# ADS1299.net
KiCad netlist of a schematic drawn in Altium Designer
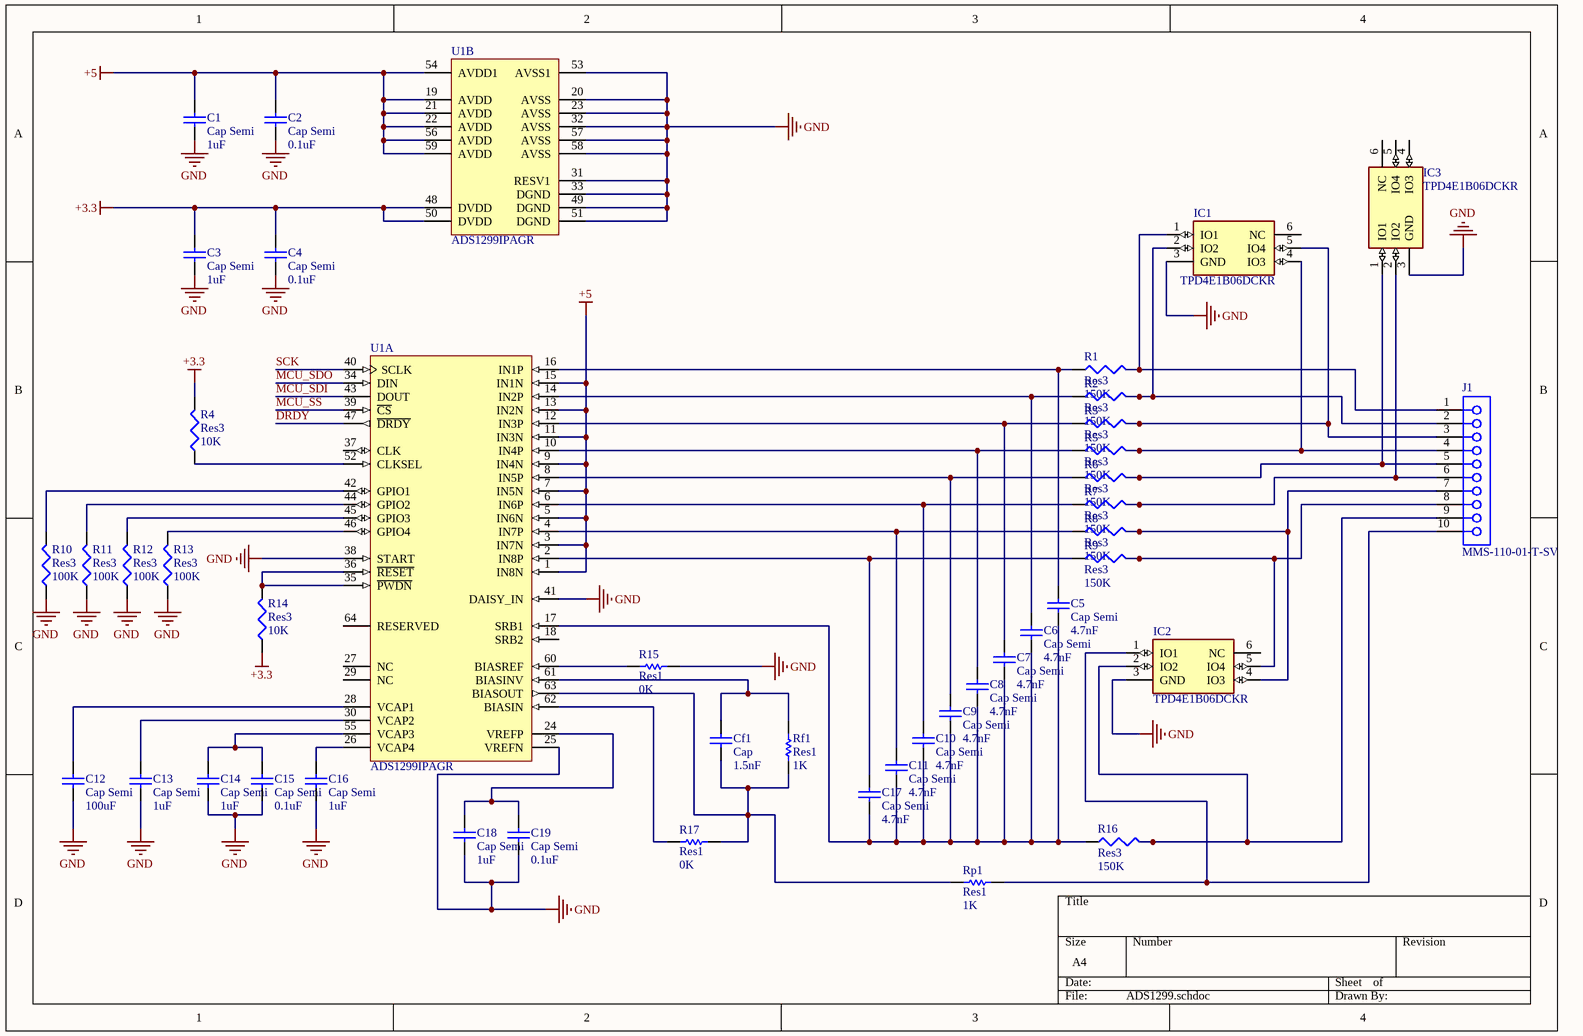
[diagram p0: ADS1299.schdoc]

(export (version "E")
  (design (tool "Eeschema 10.0.6"))
  (components
    (comp (ref "C1")
      (value "Cap Semi")
      (footprint "0805c")
      (description "Capacitor (Semiconductor SIM Model)")
      (fields (field (name "ALTIUM_VALUE") "1uF") (field (name "PUBLISHER") "Altium Limited"))
      (libsource (lib "Miscellaneous Devices") (part "Cap Semi"))
    )
    (comp (ref "C2")
      (value "Cap Semi")
      (footprint "0805c")
      (description "Capacitor (Semiconductor SIM Model)")
      (fields (field (name "ALTIUM_VALUE") "0.1uF") (field (name "PUBLISHER") "Altium Limited"))
      (libsource (lib "Miscellaneous Devices") (part "Cap Semi"))
    )
    (comp (ref "C3")
      (value "Cap Semi")
      (footprint "0805c")
      (description "Capacitor (Semiconductor SIM Model)")
      (fields (field (name "ALTIUM_VALUE") "1uF") (field (name "PUBLISHER") "Altium Limited"))
      (libsource (lib "Miscellaneous Devices") (part "Cap Semi"))
    )
    (comp (ref "C4")
      (value "Cap Semi")
      (footprint "0805c")
      (description "Capacitor (Semiconductor SIM Model)")
      (fields (field (name "ALTIUM_VALUE") "0.1uF") (field (name "PUBLISHER") "Altium Limited"))
      (libsource (lib "Miscellaneous Devices") (part "Cap Semi"))
    )
    (comp (ref "C5")
      (value "Cap Semi")
      (footprint "0805c")
      (description "Capacitor (Semiconductor SIM Model)")
      (fields (field (name "ALTIUM_VALUE") "4.7nF") (field (name "PUBLISHER") "Altium Limited"))
      (libsource (lib "Miscellaneous Devices") (part "Cap Semi"))
    )
    (comp (ref "C6")
      (value "Cap Semi")
      (footprint "0805c")
      (description "Capacitor (Semiconductor SIM Model)")
      (fields (field (name "ALTIUM_VALUE") "4.7nF") (field (name "PUBLISHER") "Altium Limited"))
      (libsource (lib "Miscellaneous Devices") (part "Cap Semi"))
    )
    (comp (ref "C7")
      (value "Cap Semi")
      (footprint "0805c")
      (description "Capacitor (Semiconductor SIM Model)")
      (fields (field (name "ALTIUM_VALUE") "4.7nF") (field (name "PUBLISHER") "Altium Limited"))
      (libsource (lib "Miscellaneous Devices") (part "Cap Semi"))
    )
    (comp (ref "C8")
      (value "Cap Semi")
      (footprint "0805c")
      (description "Capacitor (Semiconductor SIM Model)")
      (fields (field (name "ALTIUM_VALUE") "4.7nF") (field (name "PUBLISHER") "Altium Limited"))
      (libsource (lib "Miscellaneous Devices") (part "Cap Semi"))
    )
    (comp (ref "C9")
      (value "Cap Semi")
      (footprint "0805c")
      (description "Capacitor (Semiconductor SIM Model)")
      (fields (field (name "ALTIUM_VALUE") "4.7nF") (field (name "PUBLISHER") "Altium Limited"))
      (libsource (lib "Miscellaneous Devices") (part "Cap Semi"))
    )
    (comp (ref "C10")
      (value "Cap Semi")
      (footprint "0805c")
      (description "Capacitor (Semiconductor SIM Model)")
      (fields (field (name "ALTIUM_VALUE") "4.7nF") (field (name "PUBLISHER") "Altium Limited"))
      (libsource (lib "Miscellaneous Devices") (part "Cap Semi"))
    )
    (comp (ref "C11")
      (value "Cap Semi")
      (footprint "0805c")
      (description "Capacitor (Semiconductor SIM Model)")
      (fields (field (name "ALTIUM_VALUE") "4.7nF") (field (name "PUBLISHER") "Altium Limited"))
      (libsource (lib "Miscellaneous Devices") (part "Cap Semi"))
    )
    (comp (ref "C12")
      (value "Cap Semi")
      (footprint "0805c")
      (description "Capacitor (Semiconductor SIM Model)")
      (fields (field (name "ALTIUM_VALUE") "100uF") (field (name "PUBLISHER") "Altium Limited"))
      (libsource (lib "Miscellaneous Devices") (part "Cap Semi"))
    )
    (comp (ref "C13")
      (value "Cap Semi")
      (footprint "0805c")
      (description "Capacitor (Semiconductor SIM Model)")
      (fields (field (name "ALTIUM_VALUE") "1uF") (field (name "PUBLISHER") "Altium Limited"))
      (libsource (lib "Miscellaneous Devices") (part "Cap Semi"))
    )
    (comp (ref "C14")
      (value "Cap Semi")
      (footprint "0805c")
      (description "Capacitor (Semiconductor SIM Model)")
      (fields (field (name "ALTIUM_VALUE") "1uF") (field (name "PUBLISHER") "Altium Limited"))
      (libsource (lib "Miscellaneous Devices") (part "Cap Semi"))
    )
    (comp (ref "C15")
      (value "Cap Semi")
      (footprint "0805c")
      (description "Capacitor (Semiconductor SIM Model)")
      (fields (field (name "ALTIUM_VALUE") "0.1uF") (field (name "PUBLISHER") "Altium Limited"))
      (libsource (lib "Miscellaneous Devices") (part "Cap Semi"))
    )
    (comp (ref "C16")
      (value "Cap Semi")
      (footprint "0805c")
      (description "Capacitor (Semiconductor SIM Model)")
      (fields (field (name "ALTIUM_VALUE") "1uF") (field (name "PUBLISHER") "Altium Limited"))
      (libsource (lib "Miscellaneous Devices") (part "Cap Semi"))
    )
    (comp (ref "C17")
      (value "Cap Semi")
      (footprint "0805c")
      (description "Capacitor (Semiconductor SIM Model)")
      (fields (field (name "ALTIUM_VALUE") "4.7nF") (field (name "PUBLISHER") "Altium Limited"))
      (libsource (lib "Miscellaneous Devices") (part "Cap Semi"))
    )
    (comp (ref "C18")
      (value "Cap Semi")
      (footprint "0805c")
      (description "Capacitor (Semiconductor SIM Model)")
      (fields (field (name "ALTIUM_VALUE") "1uF") (field (name "PUBLISHER") "Altium Limited"))
      (libsource (lib "Miscellaneous Devices") (part "Cap Semi"))
    )
    (comp (ref "C19")
      (value "Cap Semi")
      (footprint "0805c")
      (description "Capacitor (Semiconductor SIM Model)")
      (fields (field (name "ALTIUM_VALUE") "0.1uF") (field (name "PUBLISHER") "Altium Limited"))
      (libsource (lib "Miscellaneous Devices") (part "Cap Semi"))
    )
    (comp (ref "Cf1")
      (value "Cap")
      (footprint "102")
      (description "Capacitor")
      (fields (field (name "ALTIUM_VALUE") "1.5nF") (field (name "PUBLISHER") "Altium Limited"))
      (libsource (lib "Miscellaneous Devices") (part "Cap"))
    )
    (comp (ref "IC1")
      (value "TPD4E1B06DCKR")
      (footprint "SOT363")
      (description "Integrated Circuit")
      (fields
        (field (name "MOUSER PART NUMBER") "595-TPD4E1B06DCKR")
        (field (name "RS PART NUMBER") "8255330P")
      )
      (libsource (lib "") (part "TPD4E1B06DCKR_1"))
    )
    (comp (ref "IC2")
      (value "TPD4E1B06DCKR")
      (footprint "SOT363")
      (description "Integrated Circuit")
      (fields
        (field (name "MOUSER PART NUMBER") "595-TPD4E1B06DCKR")
        (field (name "RS PART NUMBER") "8255330P")
      )
      (libsource (lib "") (part "TPD4E1B06DCKR_1"))
    )
    (comp (ref "IC3")
      (value "TPD4E1B06DCKR")
      (footprint "SOT363")
      (description "Integrated Circuit")
      (fields
        (field (name "MOUSER PART NUMBER") "595-TPD4E1B06DCKR")
        (field (name "RS PART NUMBER") "8255330P")
      )
      (libsource (lib "*") (part "TPD4E1B06DCKR"))
    )
    (comp (ref "J1")
      (value "MMS-110-01-T-SV")
      (footprint "HDR1X10")
      (fields (field (name "MANUFACTURER") "Samtec"))
      (libsource (lib "Altium Content Vault") (part "SMTC-MMS-110-01-X-SV"))
    )
    (comp (ref "R1")
      (value "Res3")
      (footprint "0805")
      (description "Resistor")
      (fields (field (name "ALTIUM_VALUE") "150K") (field (name "PUBLISHER") "Altium Limited"))
      (libsource (lib "Miscellaneous Devices") (part "Res3"))
    )
    (comp (ref "R2")
      (value "Res3")
      (footprint "0805")
      (description "Resistor")
      (fields (field (name "ALTIUM_VALUE") "150K") (field (name "PUBLISHER") "Altium Limited"))
      (libsource (lib "Miscellaneous Devices") (part "Res3"))
    )
    (comp (ref "R3")
      (value "Res3")
      (footprint "0805")
      (description "Resistor")
      (fields (field (name "ALTIUM_VALUE") "150K") (field (name "PUBLISHER") "Altium Limited"))
      (libsource (lib "Miscellaneous Devices") (part "Res3"))
    )
    (comp (ref "R4")
      (value "Res3")
      (footprint "0805")
      (description "Resistor")
      (fields (field (name "ALTIUM_VALUE") "10K") (field (name "PUBLISHER") "Altium Limited"))
      (libsource (lib "Miscellaneous Devices") (part "Res3"))
    )
    (comp (ref "R5")
      (value "Res3")
      (footprint "0805")
      (description "Resistor")
      (fields (field (name "ALTIUM_VALUE") "150K") (field (name "PUBLISHER") "Altium Limited"))
      (libsource (lib "Miscellaneous Devices") (part "Res3"))
    )
    (comp (ref "R6")
      (value "Res3")
      (footprint "0805")
      (description "Resistor")
      (fields (field (name "ALTIUM_VALUE") "150K") (field (name "PUBLISHER") "Altium Limited"))
      (libsource (lib "Miscellaneous Devices") (part "Res3"))
    )
    (comp (ref "R7")
      (value "Res3")
      (footprint "0805")
      (description "Resistor")
      (fields (field (name "ALTIUM_VALUE") "150K") (field (name "PUBLISHER") "Altium Limited"))
      (libsource (lib "Miscellaneous Devices") (part "Res3"))
    )
    (comp (ref "R8")
      (value "Res3")
      (footprint "0805")
      (description "Resistor")
      (fields (field (name "ALTIUM_VALUE") "150K") (field (name "PUBLISHER") "Altium Limited"))
      (libsource (lib "Miscellaneous Devices") (part "Res3"))
    )
    (comp (ref "R9")
      (value "Res3")
      (footprint "0805")
      (description "Resistor")
      (fields (field (name "ALTIUM_VALUE") "150K") (field (name "PUBLISHER") "Altium Limited"))
      (libsource (lib "Miscellaneous Devices") (part "Res3"))
    )
    (comp (ref "R10")
      (value "Res3")
      (footprint "0805")
      (description "Resistor")
      (fields (field (name "ALTIUM_VALUE") "100K") (field (name "PUBLISHER") "Altium Limited"))
      (libsource (lib "Miscellaneous Devices") (part "Res3"))
    )
    (comp (ref "R11")
      (value "Res3")
      (footprint "0805")
      (description "Resistor")
      (fields (field (name "ALTIUM_VALUE") "100K") (field (name "PUBLISHER") "Altium Limited"))
      (libsource (lib "Miscellaneous Devices") (part "Res3"))
    )
    (comp (ref "R12")
      (value "Res3")
      (footprint "0805")
      (description "Resistor")
      (fields (field (name "ALTIUM_VALUE") "100K") (field (name "PUBLISHER") "Altium Limited"))
      (libsource (lib "Miscellaneous Devices") (part "Res3"))
    )
    (comp (ref "R13")
      (value "Res3")
      (footprint "0805")
      (description "Resistor")
      (fields (field (name "ALTIUM_VALUE") "100K") (field (name "PUBLISHER") "Altium Limited"))
      (libsource (lib "Miscellaneous Devices") (part "Res3"))
    )
    (comp (ref "R14")
      (value "Res3")
      (footprint "0805")
      (description "Resistor")
      (fields (field (name "ALTIUM_VALUE") "10K") (field (name "PUBLISHER") "Altium Limited"))
      (libsource (lib "Miscellaneous Devices") (part "Res3"))
    )
    (comp (ref "R15")
      (value "Res1")
      (footprint "RB0.4    &9")
      (description "Resistor")
      (fields (field (name "ALTIUM_VALUE") "0K") (field (name "PUBLISHER") "Altium Limited"))
      (libsource (lib "Miscellaneous Devices") (part "Res1"))
    )
    (comp (ref "R16")
      (value "Res3")
      (footprint "0805")
      (description "Resistor")
      (fields (field (name "ALTIUM_VALUE") "150K") (field (name "PUBLISHER") "Altium Limited"))
      (libsource (lib "Miscellaneous Devices") (part "Res3"))
    )
    (comp (ref "R17")
      (value "Res1")
      (footprint "RB0.4    &9")
      (description "Resistor")
      (fields (field (name "ALTIUM_VALUE") "0K") (field (name "PUBLISHER") "Altium Limited"))
      (libsource (lib "Miscellaneous Devices") (part "Res1"))
    )
    (comp (ref "Rf1")
      (value "Res1")
      (footprint "RB0.4    &9")
      (description "Resistor")
      (fields (field (name "ALTIUM_VALUE") "1K") (field (name "PUBLISHER") "Altium Limited"))
      (libsource (lib "Miscellaneous Devices") (part "Res1"))
    )
    (comp (ref "Rp1")
      (value "Res1")
      (footprint "RB0.4    &9")
      (description "Resistor")
      (fields (field (name "ALTIUM_VALUE") "1K") (field (name "PUBLISHER") "Altium Limited"))
      (libsource (lib "Miscellaneous Devices") (part "Res1"))
    )
    (comp (ref "U1")
      (value "ADS1299IPAGR")
      (footprint "TQFP64_N")
      (fields (field (name "MANUFACTURER") "Texas Instruments"))
      (libsource (lib "Altium Content Vault") (part "TI-ADS1299-PAG-64"))
    )
  )
  (nets
    (net (code "1") (name "+3.3") (class "Default")
      (node (ref "C3") (pin "2") (pinfunction "2_2") (pintype "passive"))
      (node (ref "C4") (pin "2") (pinfunction "2_2") (pintype "passive"))
      (node (ref "R14") (pin "1") (pinfunction "1_1") (pintype "passive"))
      (node (ref "R4") (pin "2") (pinfunction "2_2") (pintype "passive"))
      (node (ref "U1") (pin "48") (pinfunction "DVDD_48") (pintype "power_in"))
      (node (ref "U1") (pin "50") (pinfunction "DVDD_50") (pintype "power_in"))
    )
    (net (code "2") (name "+5") (class "Default")
      (node (ref "C1") (pin "2") (pinfunction "2_2") (pintype "passive"))
      (node (ref "C2") (pin "2") (pinfunction "2_2") (pintype "passive"))
      (node (ref "U1") (pin "1") (pinfunction "IN8N_1") (pintype "input"))
      (node (ref "U1") (pin "11") (pinfunction "IN3N_11") (pintype "input"))
      (node (ref "U1") (pin "13") (pinfunction "IN2N_13") (pintype "input"))
      (node (ref "U1") (pin "15") (pinfunction "IN1N_15") (pintype "input"))
      (node (ref "U1") (pin "19") (pinfunction "AVDD_19") (pintype "power_in"))
      (node (ref "U1") (pin "21") (pinfunction "AVDD_21") (pintype "power_in"))
      (node (ref "U1") (pin "22") (pinfunction "AVDD_22") (pintype "power_in"))
      (node (ref "U1") (pin "3") (pinfunction "IN7N_3") (pintype "input"))
      (node (ref "U1") (pin "5") (pinfunction "IN6N_5") (pintype "input"))
      (node (ref "U1") (pin "54") (pinfunction "AVDD1_54") (pintype "power_in"))
      (node (ref "U1") (pin "56") (pinfunction "AVDD_56") (pintype "power_in"))
      (node (ref "U1") (pin "59") (pinfunction "AVDD_59") (pintype "power_in"))
      (node (ref "U1") (pin "7") (pinfunction "IN5N_7") (pintype "input"))
      (node (ref "U1") (pin "9") (pinfunction "IN4N_9") (pintype "input"))
    )
    (net (code "3") (name "/DRDY") (class "Default")
      (node (ref "U1") (pin "47") (pinfunction "~{DRDY}_47") (pintype "output"))
    )
    (net (code "4") (name "/MCU_SDI") (class "Default")
      (node (ref "U1") (pin "43") (pinfunction "DOUT_43") (pintype "tri_state"))
    )
    (net (code "5") (name "/MCU_SDO") (class "Default")
      (node (ref "U1") (pin "34") (pinfunction "DIN_34") (pintype "input"))
    )
    (net (code "6") (name "/MCU_SS") (class "Default")
      (node (ref "U1") (pin "39") (pinfunction "~{CS}_39") (pintype "input"))
    )
    (net (code "7") (name "/SCK") (class "Default")
      (node (ref "U1") (pin "40") (pinfunction "SCLK_40") (pintype "input"))
    )
    (net (code "8") (name "GND") (class "Default")
      (node (ref "C1") (pin "1") (pinfunction "1_1") (pintype "passive"))
      (node (ref "C12") (pin "1") (pinfunction "1_1") (pintype "passive"))
      (node (ref "C13") (pin "1") (pinfunction "1_1") (pintype "passive"))
      (node (ref "C14") (pin "1") (pinfunction "1_1") (pintype "passive"))
      (node (ref "C15") (pin "1") (pinfunction "1_1") (pintype "passive"))
      (node (ref "C16") (pin "1") (pinfunction "1_1") (pintype "passive"))
      (node (ref "C18") (pin "1") (pinfunction "1_1") (pintype "passive"))
      (node (ref "C19") (pin "1") (pinfunction "1_1") (pintype "passive"))
      (node (ref "C2") (pin "1") (pinfunction "1_1") (pintype "passive"))
      (node (ref "C3") (pin "1") (pinfunction "1_1") (pintype "passive"))
      (node (ref "C4") (pin "1") (pinfunction "1_1") (pintype "passive"))
      (node (ref "IC1") (pin "3") (pinfunction "GND_3") (pintype "power_in"))
      (node (ref "IC2") (pin "3") (pinfunction "GND_3") (pintype "power_in"))
      (node (ref "IC3") (pin "3") (pinfunction "GND_3") (pintype "power_in"))
      (node (ref "R10") (pin "1") (pinfunction "1_1") (pintype "passive"))
      (node (ref "R11") (pin "1") (pinfunction "1_1") (pintype "passive"))
      (node (ref "R12") (pin "1") (pinfunction "1_1") (pintype "passive"))
      (node (ref "R13") (pin "1") (pinfunction "1_1") (pintype "passive"))
      (node (ref "R15") (pin "1") (pinfunction "1_1") (pintype "passive"))
      (node (ref "U1") (pin "20") (pinfunction "AVSS_20") (pintype "power_in"))
      (node (ref "U1") (pin "23") (pinfunction "AVSS_23") (pintype "power_in"))
      (node (ref "U1") (pin "25") (pinfunction "VREFN_25") (pintype "passive"))
      (node (ref "U1") (pin "31") (pinfunction "RESV1_31") (pintype "power_in"))
      (node (ref "U1") (pin "32") (pinfunction "AVSS_32") (pintype "power_in"))
      (node (ref "U1") (pin "33") (pinfunction "DGND_33") (pintype "power_in"))
      (node (ref "U1") (pin "38") (pinfunction "START_38") (pintype "input"))
      (node (ref "U1") (pin "41") (pinfunction "DAISY_IN_41") (pintype "input"))
      (node (ref "U1") (pin "49") (pinfunction "DGND_49") (pintype "power_in"))
      (node (ref "U1") (pin "51") (pinfunction "DGND_51") (pintype "power_in"))
      (node (ref "U1") (pin "53") (pinfunction "AVSS1_53") (pintype "power_in"))
      (node (ref "U1") (pin "57") (pinfunction "AVSS_57") (pintype "power_in"))
      (node (ref "U1") (pin "58") (pinfunction "AVSS_58") (pintype "power_in"))
    )
    (net (code "9") (name "Net-(IC1-IO1)") (class "Default")
      (node (ref "IC1") (pin "1") (pinfunction "IO1_1") (pintype "bidirectional"))
      (node (ref "J1") (pin "1") (pinfunction "1_1") (pintype "passive"))
      (node (ref "R1") (pin "2") (pinfunction "2_2") (pintype "passive"))
    )
    (net (code "10") (name "Net-(IC1-IO2)") (class "Default")
      (node (ref "IC1") (pin "2") (pinfunction "IO2_2") (pintype "bidirectional"))
      (node (ref "J1") (pin "2") (pinfunction "2_2") (pintype "passive"))
      (node (ref "R2") (pin "2") (pinfunction "2_2") (pintype "passive"))
    )
    (net (code "11") (name "Net-(IC1-IO3)") (class "Default")
      (node (ref "IC1") (pin "4") (pinfunction "IO3_4") (pintype "bidirectional"))
      (node (ref "J1") (pin "4") (pinfunction "4_4") (pintype "passive"))
      (node (ref "R5") (pin "2") (pinfunction "2_2") (pintype "passive"))
    )
    (net (code "12") (name "Net-(IC1-IO4)") (class "Default")
      (node (ref "IC1") (pin "5") (pinfunction "IO4_5") (pintype "bidirectional"))
      (node (ref "J1") (pin "3") (pinfunction "3_3") (pintype "passive"))
      (node (ref "R3") (pin "2") (pinfunction "2_2") (pintype "passive"))
    )
    (net (code "13") (name "Net-(IC2-IO1)") (class "Default")
      (node (ref "IC2") (pin "1") (pinfunction "IO1_1") (pintype "bidirectional"))
      (node (ref "J1") (pin "10") (pinfunction "10_10") (pintype "passive"))
      (node (ref "Rp1") (pin "2") (pinfunction "2_2") (pintype "passive"))
    )
    (net (code "14") (name "Net-(IC2-IO2)") (class "Default")
      (node (ref "IC2") (pin "2") (pinfunction "IO2_2") (pintype "bidirectional"))
      (node (ref "J1") (pin "9") (pinfunction "9_9") (pintype "passive"))
      (node (ref "R16") (pin "2") (pinfunction "2_2") (pintype "passive"))
    )
    (net (code "15") (name "Net-(IC2-IO3)") (class "Default")
      (node (ref "IC2") (pin "4") (pinfunction "IO3_4") (pintype "bidirectional"))
      (node (ref "J1") (pin "7") (pinfunction "7_7") (pintype "passive"))
      (node (ref "R8") (pin "2") (pinfunction "2_2") (pintype "passive"))
    )
    (net (code "16") (name "Net-(IC2-IO4)") (class "Default")
      (node (ref "IC2") (pin "5") (pinfunction "IO4_5") (pintype "bidirectional"))
      (node (ref "J1") (pin "8") (pinfunction "8_8") (pintype "passive"))
      (node (ref "R9") (pin "2") (pinfunction "2_2") (pintype "passive"))
    )
    (net (code "17") (name "Net-(IC3-IO1)") (class "Default")
      (node (ref "IC3") (pin "1") (pinfunction "IO1_1") (pintype "bidirectional"))
      (node (ref "J1") (pin "5") (pinfunction "5_5") (pintype "passive"))
      (node (ref "R6") (pin "2") (pinfunction "2_2") (pintype "passive"))
    )
    (net (code "18") (name "Net-(IC3-IO2)") (class "Default")
      (node (ref "IC3") (pin "2") (pinfunction "IO2_2") (pintype "bidirectional"))
      (node (ref "J1") (pin "6") (pinfunction "6_6") (pintype "passive"))
      (node (ref "R7") (pin "2") (pinfunction "2_2") (pintype "passive"))
    )
    (net (code "19") (name "Net-(U1A-BIASIN)") (class "Default")
      (node (ref "R17") (pin "1") (pinfunction "1_1") (pintype "passive"))
      (node (ref "U1") (pin "62") (pinfunction "BIASIN_62") (pintype "input"))
    )
    (net (code "20") (name "Net-(U1A-BIASINV)") (class "Default")
      (node (ref "Cf1") (pin "2") (pinfunction "2_2") (pintype "passive"))
      (node (ref "Rf1") (pin "2") (pinfunction "2_2") (pintype "passive"))
      (node (ref "U1") (pin "61") (pinfunction "BIASINV_61") (pintype "input"))
    )
    (net (code "21") (name "Net-(U1A-BIASOUT)") (class "Default")
      (node (ref "Cf1") (pin "1") (pinfunction "1_1") (pintype "passive"))
      (node (ref "R17") (pin "2") (pinfunction "2_2") (pintype "passive"))
      (node (ref "Rf1") (pin "1") (pinfunction "1_1") (pintype "passive"))
      (node (ref "Rp1") (pin "1") (pinfunction "1_1") (pintype "passive"))
      (node (ref "U1") (pin "63") (pinfunction "BIASOUT_63") (pintype "output"))
    )
    (net (code "22") (name "Net-(U1A-BIASREF)") (class "Default")
      (node (ref "R15") (pin "2") (pinfunction "2_2") (pintype "passive"))
      (node (ref "U1") (pin "60") (pinfunction "BIASREF_60") (pintype "input"))
    )
    (net (code "23") (name "Net-(U1A-CLKSEL)") (class "Default")
      (node (ref "R4") (pin "1") (pinfunction "1_1") (pintype "passive"))
      (node (ref "U1") (pin "52") (pinfunction "CLKSEL_52") (pintype "input"))
    )
    (net (code "24") (name "Net-(U1A-GPIO1)") (class "Default")
      (node (ref "R10") (pin "2") (pinfunction "2_2") (pintype "passive"))
      (node (ref "U1") (pin "42") (pinfunction "GPIO1_42") (pintype "bidirectional"))
    )
    (net (code "25") (name "Net-(U1A-GPIO2)") (class "Default")
      (node (ref "R11") (pin "2") (pinfunction "2_2") (pintype "passive"))
      (node (ref "U1") (pin "44") (pinfunction "GPIO2_44") (pintype "bidirectional"))
    )
    (net (code "26") (name "Net-(U1A-GPIO3)") (class "Default")
      (node (ref "R12") (pin "2") (pinfunction "2_2") (pintype "passive"))
      (node (ref "U1") (pin "45") (pinfunction "GPIO3_45") (pintype "bidirectional"))
    )
    (net (code "27") (name "Net-(U1A-GPIO4)") (class "Default")
      (node (ref "R13") (pin "2") (pinfunction "2_2") (pintype "passive"))
      (node (ref "U1") (pin "46") (pinfunction "GPIO4_46") (pintype "bidirectional"))
    )
    (net (code "28") (name "Net-(U1A-IN1P)") (class "Default")
      (node (ref "C5") (pin "2") (pinfunction "2_2") (pintype "passive"))
      (node (ref "R1") (pin "1") (pinfunction "1_1") (pintype "passive"))
      (node (ref "U1") (pin "16") (pinfunction "IN1P_16") (pintype "input"))
    )
    (net (code "29") (name "Net-(U1A-IN2P)") (class "Default")
      (node (ref "C6") (pin "2") (pinfunction "2_2") (pintype "passive"))
      (node (ref "R2") (pin "1") (pinfunction "1_1") (pintype "passive"))
      (node (ref "U1") (pin "14") (pinfunction "IN2P_14") (pintype "input"))
    )
    (net (code "30") (name "Net-(U1A-IN3P)") (class "Default")
      (node (ref "C7") (pin "2") (pinfunction "2_2") (pintype "passive"))
      (node (ref "R3") (pin "1") (pinfunction "1_1") (pintype "passive"))
      (node (ref "U1") (pin "12") (pinfunction "IN3P_12") (pintype "input"))
    )
    (net (code "31") (name "Net-(U1A-IN4P)") (class "Default")
      (node (ref "C8") (pin "2") (pinfunction "2_2") (pintype "passive"))
      (node (ref "R5") (pin "1") (pinfunction "1_1") (pintype "passive"))
      (node (ref "U1") (pin "10") (pinfunction "IN4P_10") (pintype "input"))
    )
    (net (code "32") (name "Net-(U1A-IN5P)") (class "Default")
      (node (ref "C9") (pin "2") (pinfunction "2_2") (pintype "passive"))
      (node (ref "R6") (pin "1") (pinfunction "1_1") (pintype "passive"))
      (node (ref "U1") (pin "8") (pinfunction "IN5P_8") (pintype "input"))
    )
    (net (code "33") (name "Net-(U1A-IN6P)") (class "Default")
      (node (ref "C10") (pin "2") (pinfunction "2_2") (pintype "passive"))
      (node (ref "R7") (pin "1") (pinfunction "1_1") (pintype "passive"))
      (node (ref "U1") (pin "6") (pinfunction "IN6P_6") (pintype "input"))
    )
    (net (code "34") (name "Net-(U1A-IN7P)") (class "Default")
      (node (ref "C11") (pin "2") (pinfunction "2_2") (pintype "passive"))
      (node (ref "R8") (pin "1") (pinfunction "1_1") (pintype "passive"))
      (node (ref "U1") (pin "4") (pinfunction "IN7P_4") (pintype "input"))
    )
    (net (code "35") (name "Net-(U1A-IN8P)") (class "Default")
      (node (ref "C17") (pin "2") (pinfunction "2_2") (pintype "passive"))
      (node (ref "R9") (pin "1") (pinfunction "1_1") (pintype "passive"))
      (node (ref "U1") (pin "2") (pinfunction "IN8P_2") (pintype "input"))
    )
    (net (code "36") (name "Net-(U1A-SRB1)") (class "Default")
      (node (ref "C10") (pin "1") (pinfunction "1_1") (pintype "passive"))
      (node (ref "C11") (pin "1") (pinfunction "1_1") (pintype "passive"))
      (node (ref "C17") (pin "1") (pinfunction "1_1") (pintype "passive"))
      (node (ref "C5") (pin "1") (pinfunction "1_1") (pintype "passive"))
      (node (ref "C6") (pin "1") (pinfunction "1_1") (pintype "passive"))
      (node (ref "C7") (pin "1") (pinfunction "1_1") (pintype "passive"))
      (node (ref "C8") (pin "1") (pinfunction "1_1") (pintype "passive"))
      (node (ref "C9") (pin "1") (pinfunction "1_1") (pintype "passive"))
      (node (ref "R16") (pin "1") (pinfunction "1_1") (pintype "passive"))
      (node (ref "U1") (pin "17") (pinfunction "SRB1_17") (pintype "input"))
    )
    (net (code "37") (name "Net-(U1A-VCAP1)") (class "Default")
      (node (ref "C12") (pin "2") (pinfunction "2_2") (pintype "passive"))
      (node (ref "U1") (pin "28") (pinfunction "VCAP1_28") (pintype "passive"))
    )
    (net (code "38") (name "Net-(U1A-VCAP2)") (class "Default")
      (node (ref "C13") (pin "2") (pinfunction "2_2") (pintype "passive"))
      (node (ref "U1") (pin "30") (pinfunction "VCAP2_30") (pintype "passive"))
    )
    (net (code "39") (name "Net-(U1A-VCAP3)") (class "Default")
      (node (ref "C14") (pin "2") (pinfunction "2_2") (pintype "passive"))
      (node (ref "C15") (pin "2") (pinfunction "2_2") (pintype "passive"))
      (node (ref "U1") (pin "55") (pinfunction "VCAP3_55") (pintype "passive"))
    )
    (net (code "40") (name "Net-(U1A-VCAP4)") (class "Default")
      (node (ref "C16") (pin "2") (pinfunction "2_2") (pintype "passive"))
      (node (ref "U1") (pin "26") (pinfunction "VCAP4_26") (pintype "passive"))
    )
    (net (code "41") (name "Net-(U1A-VREFP)") (class "Default")
      (node (ref "C18") (pin "2") (pinfunction "2_2") (pintype "passive"))
      (node (ref "C19") (pin "2") (pinfunction "2_2") (pintype "passive"))
      (node (ref "U1") (pin "24") (pinfunction "VREFP_24") (pintype "passive"))
    )
    (net (code "42") (name "Net-(U1A-~{PWDN})") (class "Default")
      (node (ref "R14") (pin "2") (pinfunction "2_2") (pintype "passive"))
      (node (ref "U1") (pin "35") (pinfunction "~{PWDN}_35") (pintype "input"))
      (node (ref "U1") (pin "36") (pinfunction "~{RESET}_36") (pintype "input"))
    )
    (net (code "43") (name "unconnected-(IC1-NC-Pad6)") (class "Default")
      (node (ref "IC1") (pin "6") (pinfunction "NC_6") (pintype "passive"))
    )
    (net (code "44") (name "unconnected-(IC2-NC-Pad6)") (class "Default")
      (node (ref "IC2") (pin "6") (pinfunction "NC_6") (pintype "passive"))
    )
    (net (code "45") (name "unconnected-(IC3-IO3-Pad4)") (class "Default")
      (node (ref "IC3") (pin "4") (pinfunction "IO3_4") (pintype "bidirectional"))
    )
    (net (code "46") (name "unconnected-(IC3-IO4-Pad5)") (class "Default")
      (node (ref "IC3") (pin "5") (pinfunction "IO4_5") (pintype "bidirectional"))
    )
    (net (code "47") (name "unconnected-(IC3-NC-Pad6)") (class "Default")
      (node (ref "IC3") (pin "6") (pinfunction "NC_6") (pintype "passive"))
    )
    (net (code "48") (name "unconnected-(U1A-CLK-Pad37)") (class "Default")
      (node (ref "U1") (pin "37") (pinfunction "CLK_37") (pintype "bidirectional"))
    )
    (net (code "49") (name "unconnected-(U1A-NC-Pad27)") (class "Default")
      (node (ref "U1") (pin "27") (pinfunction "NC_27") (pintype "passive"))
    )
    (net (code "50") (name "unconnected-(U1A-NC-Pad29)") (class "Default")
      (node (ref "U1") (pin "29") (pinfunction "NC_29") (pintype "passive"))
    )
    (net (code "51") (name "unconnected-(U1A-RESERVED-Pad64)") (class "Default")
      (node (ref "U1") (pin "64") (pinfunction "RESERVED_64") (pintype "passive"))
    )
    (net (code "52") (name "unconnected-(U1A-SRB2-Pad18)") (class "Default")
      (node (ref "U1") (pin "18") (pinfunction "SRB2_18") (pintype "input"))
    )
  )
)
